# BOARD1A.net
KiCad netlist of a schematic drawn in EAGLE
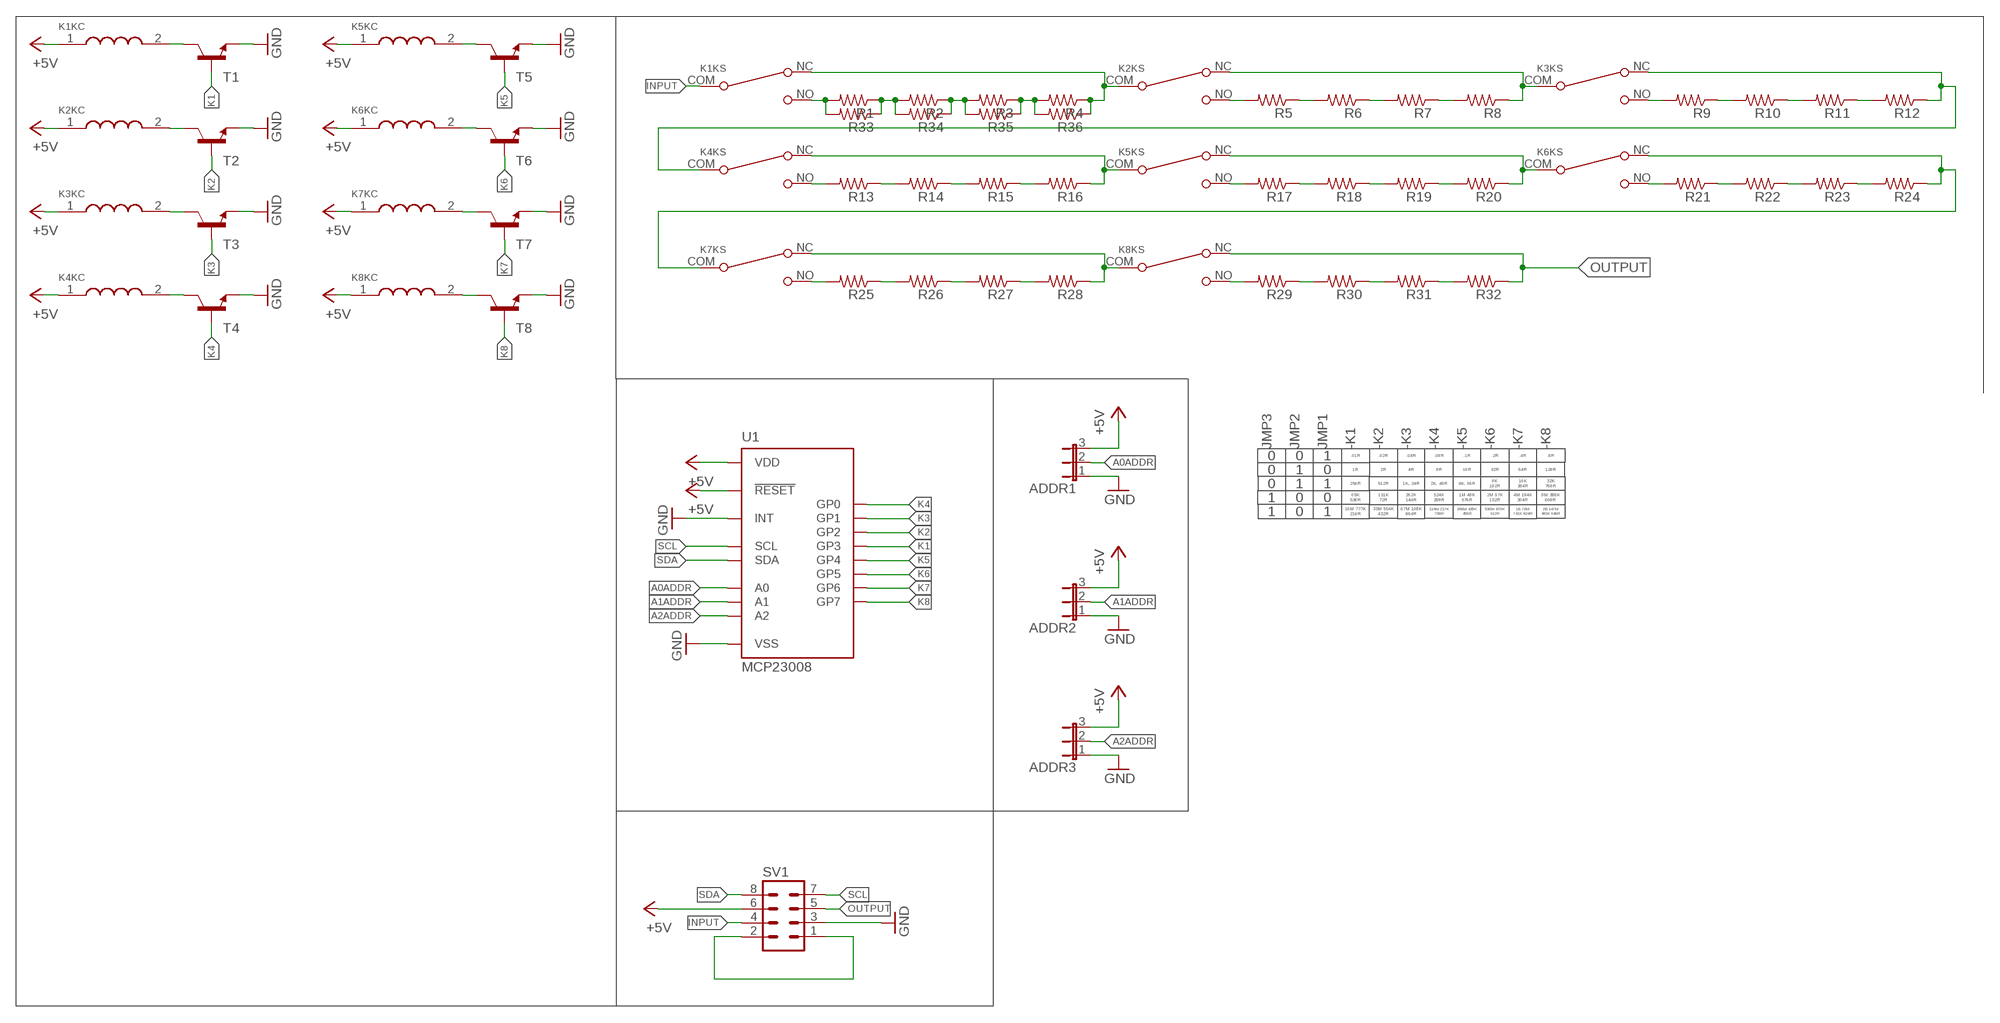
[diagram p0: schematic, sheet 1]

(export (version "E")
  (design (tool "Eeschema 10.0.6"))
  (components
    (comp (ref "ADDR1")
      (value "JP2E")
      (footprint "eagle-import:JP2")
      (libsource (lib "eagle-import") (part "JP2E"))
    )
    (comp (ref "ADDR2")
      (value "JP2E")
      (footprint "eagle-import:JP2")
      (libsource (lib "eagle-import") (part "JP2E"))
    )
    (comp (ref "ADDR3")
      (value "JP2E")
      (footprint "eagle-import:JP2")
      (libsource (lib "eagle-import") (part "JP2E"))
    )
    (comp (ref "K1")
      (value "G5LE-1-VD DC12")
      (footprint "eagle-import:G5LE")
      (libsource (lib "eagle-import") (part "G5LE"))
    )
    (comp (ref "K2")
      (value "G5LE")
      (footprint "eagle-import:G5LE")
      (libsource (lib "eagle-import") (part "G5LE"))
    )
    (comp (ref "K3")
      (value "G5LE")
      (footprint "eagle-import:G5LE")
      (libsource (lib "eagle-import") (part "G5LE"))
    )
    (comp (ref "K4")
      (value "G5LE")
      (footprint "eagle-import:G5LE")
      (libsource (lib "eagle-import") (part "G5LE"))
    )
    (comp (ref "K5")
      (value "G5LE")
      (footprint "eagle-import:G5LE")
      (libsource (lib "eagle-import") (part "G5LE"))
    )
    (comp (ref "K6")
      (value "G5LE")
      (footprint "eagle-import:G5LE")
      (libsource (lib "eagle-import") (part "G5LE"))
    )
    (comp (ref "K7")
      (value "G5LE")
      (footprint "eagle-import:G5LE")
      (libsource (lib "eagle-import") (part "G5LE"))
    )
    (comp (ref "K8")
      (value "G5LE")
      (footprint "eagle-import:G5LE")
      (libsource (lib "eagle-import") (part "G5LE"))
    )
    (comp (ref "R1")
      (value "R-US_0207/12")
      (footprint "eagle-import:0207_12")
      (libsource (lib "eagle-import") (part "R-US_0207/12"))
    )
    (comp (ref "R2")
      (value "R-US_0207/12")
      (footprint "eagle-import:0207_12")
      (libsource (lib "eagle-import") (part "R-US_0207/12"))
    )
    (comp (ref "R3")
      (value "R-US_0207/12")
      (footprint "eagle-import:0207_12")
      (libsource (lib "eagle-import") (part "R-US_0207/12"))
    )
    (comp (ref "R4")
      (value "R-US_0207/12")
      (footprint "eagle-import:0207_12")
      (libsource (lib "eagle-import") (part "R-US_0207/12"))
    )
    (comp (ref "R5")
      (value "R-US_0207/12")
      (footprint "eagle-import:0207_12")
      (libsource (lib "eagle-import") (part "R-US_0207/12"))
    )
    (comp (ref "R6")
      (value "R-US_0207/12")
      (footprint "eagle-import:0207_12")
      (libsource (lib "eagle-import") (part "R-US_0207/12"))
    )
    (comp (ref "R7")
      (value "R-US_0207/12")
      (footprint "eagle-import:0207_12")
      (libsource (lib "eagle-import") (part "R-US_0207/12"))
    )
    (comp (ref "R8")
      (value "R-US_0207/12")
      (footprint "eagle-import:0207_12")
      (libsource (lib "eagle-import") (part "R-US_0207/12"))
    )
    (comp (ref "R9")
      (value "R-US_0207/12")
      (footprint "eagle-import:0207_12")
      (libsource (lib "eagle-import") (part "R-US_0207/12"))
    )
    (comp (ref "R10")
      (value "R-US_0207/12")
      (footprint "eagle-import:0207_12")
      (libsource (lib "eagle-import") (part "R-US_0207/12"))
    )
    (comp (ref "R11")
      (value "R-US_0207/12")
      (footprint "eagle-import:0207_12")
      (libsource (lib "eagle-import") (part "R-US_0207/12"))
    )
    (comp (ref "R12")
      (value "R-US_0207/12")
      (footprint "eagle-import:0207_12")
      (libsource (lib "eagle-import") (part "R-US_0207/12"))
    )
    (comp (ref "R13")
      (value "R-US_0207/12")
      (footprint "eagle-import:0207_12")
      (libsource (lib "eagle-import") (part "R-US_0207/12"))
    )
    (comp (ref "R14")
      (value "R-US_0207/12")
      (footprint "eagle-import:0207_12")
      (libsource (lib "eagle-import") (part "R-US_0207/12"))
    )
    (comp (ref "R15")
      (value "R-US_0207/12")
      (footprint "eagle-import:0207_12")
      (libsource (lib "eagle-import") (part "R-US_0207/12"))
    )
    (comp (ref "R16")
      (value "R-US_0207/12")
      (footprint "eagle-import:0207_12")
      (libsource (lib "eagle-import") (part "R-US_0207/12"))
    )
    (comp (ref "R17")
      (value "R-US_0207/12")
      (footprint "eagle-import:0207_12")
      (libsource (lib "eagle-import") (part "R-US_0207/12"))
    )
    (comp (ref "R18")
      (value "R-US_0207/12")
      (footprint "eagle-import:0207_12")
      (libsource (lib "eagle-import") (part "R-US_0207/12"))
    )
    (comp (ref "R19")
      (value "R-US_0207/12")
      (footprint "eagle-import:0207_12")
      (libsource (lib "eagle-import") (part "R-US_0207/12"))
    )
    (comp (ref "R20")
      (value "R-US_0207/12")
      (footprint "eagle-import:0207_12")
      (libsource (lib "eagle-import") (part "R-US_0207/12"))
    )
    (comp (ref "R21")
      (value "R-US_0207/12")
      (footprint "eagle-import:0207_12")
      (libsource (lib "eagle-import") (part "R-US_0207/12"))
    )
    (comp (ref "R22")
      (value "R-US_0207/12")
      (footprint "eagle-import:0207_12")
      (libsource (lib "eagle-import") (part "R-US_0207/12"))
    )
    (comp (ref "R23")
      (value "R-US_0207/12")
      (footprint "eagle-import:0207_12")
      (libsource (lib "eagle-import") (part "R-US_0207/12"))
    )
    (comp (ref "R24")
      (value "R-US_0207/12")
      (footprint "eagle-import:0207_12")
      (libsource (lib "eagle-import") (part "R-US_0207/12"))
    )
    (comp (ref "R25")
      (value "R-US_0207/12")
      (footprint "eagle-import:0207_12")
      (libsource (lib "eagle-import") (part "R-US_0207/12"))
    )
    (comp (ref "R26")
      (value "R-US_0207/12")
      (footprint "eagle-import:0207_12")
      (libsource (lib "eagle-import") (part "R-US_0207/12"))
    )
    (comp (ref "R27")
      (value "R-US_0207/12")
      (footprint "eagle-import:0207_12")
      (libsource (lib "eagle-import") (part "R-US_0207/12"))
    )
    (comp (ref "R28")
      (value "R-US_0207/12")
      (footprint "eagle-import:0207_12")
      (libsource (lib "eagle-import") (part "R-US_0207/12"))
    )
    (comp (ref "R29")
      (value "R-US_0207/12")
      (footprint "eagle-import:0207_12")
      (libsource (lib "eagle-import") (part "R-US_0207/12"))
    )
    (comp (ref "R30")
      (value "R-US_0207/12")
      (footprint "eagle-import:0207_12")
      (libsource (lib "eagle-import") (part "R-US_0207/12"))
    )
    (comp (ref "R31")
      (value "R-US_0207/12")
      (footprint "eagle-import:0207_12")
      (libsource (lib "eagle-import") (part "R-US_0207/12"))
    )
    (comp (ref "R32")
      (value "R-US_0207/12")
      (footprint "eagle-import:0207_12")
      (libsource (lib "eagle-import") (part "R-US_0207/12"))
    )
    (comp (ref "R33")
      (value "RESISTOR1206")
      (footprint "eagle-import:1206")
      (libsource (lib "eagle-import") (part "RESISTOR1206"))
    )
    (comp (ref "R34")
      (value "RESISTOR1206")
      (footprint "eagle-import:1206")
      (libsource (lib "eagle-import") (part "RESISTOR1206"))
    )
    (comp (ref "R35")
      (value "RESISTOR1206")
      (footprint "eagle-import:1206")
      (libsource (lib "eagle-import") (part "RESISTOR1206"))
    )
    (comp (ref "R36")
      (value "RESISTOR1206")
      (footprint "eagle-import:1206")
      (libsource (lib "eagle-import") (part "RESISTOR1206"))
    )
    (comp (ref "SV1")
      (value "MA04-2")
      (footprint "eagle-import:MA04-2")
      (libsource (lib "eagle-import") (part "MA04-2"))
    )
    (comp (ref "T1")
      (value "MMUN2211LT1-NPN-SC59-BEC")
      (footprint "eagle-import:SC59-BEC")
      (libsource (lib "eagle-import") (part "-NPN-SC59-BECMMUN2211LT1"))
    )
    (comp (ref "T2")
      (value "MMUN2211LT1-NPN-SC59-BEC")
      (footprint "eagle-import:SC59-BEC")
      (libsource (lib "eagle-import") (part "-NPN-SC59-BECMMUN2211LT1"))
    )
    (comp (ref "T3")
      (value "MMUN2211LT1-NPN-SC59-BEC")
      (footprint "eagle-import:SC59-BEC")
      (libsource (lib "eagle-import") (part "-NPN-SC59-BECMMUN2211LT1"))
    )
    (comp (ref "T4")
      (value "MMUN2211LT1-NPN-SC59-BEC")
      (footprint "eagle-import:SC59-BEC")
      (libsource (lib "eagle-import") (part "-NPN-SC59-BECMMUN2211LT1"))
    )
    (comp (ref "T5")
      (value "MMUN2211LT1-NPN-SC59-BEC")
      (footprint "eagle-import:SC59-BEC")
      (libsource (lib "eagle-import") (part "-NPN-SC59-BECMMUN2211LT1"))
    )
    (comp (ref "T6")
      (value "MMUN2211LT1-NPN-SC59-BEC")
      (footprint "eagle-import:SC59-BEC")
      (libsource (lib "eagle-import") (part "-NPN-SC59-BECMMUN2211LT1"))
    )
    (comp (ref "T7")
      (value "MMUN2211LT1-NPN-SC59-BEC")
      (footprint "eagle-import:SC59-BEC")
      (libsource (lib "eagle-import") (part "-NPN-SC59-BECMMUN2211LT1"))
    )
    (comp (ref "T8")
      (value "MMUN2211LT1-NPN-SC59-BEC")
      (footprint "eagle-import:SC59-BEC")
      (libsource (lib "eagle-import") (part "-NPN-SC59-BECMMUN2211LT1"))
    )
    (comp (ref "U1")
      (value "MCP23008")
      (footprint "eagle-import:SOIC")
      (libsource (lib "eagle-import") (part "MCP23008"))
    )
  )
  (nets
    (net (code "1") (name "+5V") (class "Default")
      (node (ref "ADDR1") (pin "3") (pinfunction "3_3") (pintype "passive"))
      (node (ref "ADDR2") (pin "3") (pinfunction "3_3") (pintype "passive"))
      (node (ref "ADDR3") (pin "3") (pinfunction "3_3") (pintype "passive"))
      (node (ref "K1") (pin "1") (pinfunction "COILA_1") (pintype "bidirectional"))
      (node (ref "K2") (pin "1") (pinfunction "COILA_1") (pintype "bidirectional"))
      (node (ref "K3") (pin "1") (pinfunction "COILA_1") (pintype "bidirectional"))
      (node (ref "K4") (pin "1") (pinfunction "COILA_1") (pintype "bidirectional"))
      (node (ref "K5") (pin "1") (pinfunction "COILA_1") (pintype "bidirectional"))
      (node (ref "K6") (pin "1") (pinfunction "COILA_1") (pintype "bidirectional"))
      (node (ref "K7") (pin "1") (pinfunction "COILA_1") (pintype "bidirectional"))
      (node (ref "K8") (pin "1") (pinfunction "COILA_1") (pintype "bidirectional"))
      (node (ref "SV1") (pin "6") (pinfunction "6_6") (pintype "passive"))
      (node (ref "U1") (pin "P$18") (pinfunction "VDD_P$18") (pintype "power_in"))
      (node (ref "U1") (pin "P$6") (pinfunction "~{RESET}_P$6") (pintype "input"))
    )
    (net (code "2") (name "A0ADDR") (class "Default")
      (node (ref "ADDR1") (pin "2") (pinfunction "2_2") (pintype "passive"))
      (node (ref "U1") (pin "P$5") (pinfunction "A0_P$5") (pintype "input"))
    )
    (net (code "3") (name "A1ADDR") (class "Default")
      (node (ref "ADDR2") (pin "2") (pinfunction "2_2") (pintype "passive"))
      (node (ref "U1") (pin "P$4") (pinfunction "A1_P$4") (pintype "input"))
    )
    (net (code "4") (name "A2ADDR") (class "Default")
      (node (ref "ADDR3") (pin "2") (pinfunction "2_2") (pintype "passive"))
      (node (ref "U1") (pin "P$3") (pinfunction "A2_P$3") (pintype "input"))
    )
    (net (code "5") (name "GND") (class "Default")
      (node (ref "ADDR1") (pin "1") (pinfunction "1_1") (pintype "passive"))
      (node (ref "ADDR2") (pin "1") (pinfunction "1_1") (pintype "passive"))
      (node (ref "ADDR3") (pin "1") (pinfunction "1_1") (pintype "passive"))
      (node (ref "SV1") (pin "3") (pinfunction "3_3") (pintype "passive"))
      (node (ref "T1") (pin "E") (pinfunction "E_E") (pintype "passive"))
      (node (ref "T2") (pin "E") (pinfunction "E_E") (pintype "passive"))
      (node (ref "T3") (pin "E") (pinfunction "E_E") (pintype "passive"))
      (node (ref "T4") (pin "E") (pinfunction "E_E") (pintype "passive"))
      (node (ref "T5") (pin "E") (pinfunction "E_E") (pintype "passive"))
      (node (ref "T6") (pin "E") (pinfunction "E_E") (pintype "passive"))
      (node (ref "T7") (pin "E") (pinfunction "E_E") (pintype "passive"))
      (node (ref "T8") (pin "E") (pinfunction "E_E") (pintype "passive"))
      (node (ref "U1") (pin "P$8") (pinfunction "INT_P$8") (pintype "output"))
      (node (ref "U1") (pin "P$9") (pinfunction "VSS_P$9") (pintype "power_in"))
    )
    (net (code "6") (name "INPUT") (class "Default")
      (node (ref "K1") (pin "COM") (pinfunction "P$COM_COM") (pintype "bidirectional"))
      (node (ref "SV1") (pin "4") (pinfunction "4_4") (pintype "passive"))
    )
    (net (code "7") (name "K1") (class "Default")
      (node (ref "T1") (pin "B") (pinfunction "B_B") (pintype "passive"))
      (node (ref "U1") (pin "P$13") (pinfunction "GP3_P$13") (pintype "bidirectional"))
    )
    (net (code "8") (name "K2") (class "Default")
      (node (ref "T2") (pin "B") (pinfunction "B_B") (pintype "passive"))
      (node (ref "U1") (pin "P$12") (pinfunction "GP2_P$12") (pintype "bidirectional"))
    )
    (net (code "9") (name "K3") (class "Default")
      (node (ref "T3") (pin "B") (pinfunction "B_B") (pintype "passive"))
      (node (ref "U1") (pin "P$11") (pinfunction "GP1_P$11") (pintype "bidirectional"))
    )
    (net (code "10") (name "K4") (class "Default")
      (node (ref "T4") (pin "B") (pinfunction "B_B") (pintype "passive"))
      (node (ref "U1") (pin "P$10") (pinfunction "GP0_P$10") (pintype "bidirectional"))
    )
    (net (code "11") (name "K5") (class "Default")
      (node (ref "T5") (pin "B") (pinfunction "B_B") (pintype "passive"))
      (node (ref "U1") (pin "P$14") (pinfunction "GP4_P$14") (pintype "bidirectional"))
    )
    (net (code "12") (name "K6") (class "Default")
      (node (ref "T6") (pin "B") (pinfunction "B_B") (pintype "passive"))
      (node (ref "U1") (pin "P$15") (pinfunction "GP5_P$15") (pintype "bidirectional"))
    )
    (net (code "13") (name "K7") (class "Default")
      (node (ref "T7") (pin "B") (pinfunction "B_B") (pintype "passive"))
      (node (ref "U1") (pin "P$16") (pinfunction "GP6_P$16") (pintype "bidirectional"))
    )
    (net (code "14") (name "K8") (class "Default")
      (node (ref "T8") (pin "B") (pinfunction "B_B") (pintype "passive"))
      (node (ref "U1") (pin "P$17") (pinfunction "GP7_P$17") (pintype "bidirectional"))
    )
    (net (code "15") (name "Net-(K1A-COILB)") (class "Default")
      (node (ref "K1") (pin "2") (pinfunction "COILB_2") (pintype "bidirectional"))
      (node (ref "T1") (pin "C") (pinfunction "C_C") (pintype "passive"))
    )
    (net (code "16") (name "Net-(K1B-P$NC)") (class "Default")
      (node (ref "K1") (pin "NC") (pinfunction "P$NC_NC") (pintype "bidirectional"))
      (node (ref "K2") (pin "COM") (pinfunction "P$COM_COM") (pintype "bidirectional"))
      (node (ref "R36") (pin "1") (pinfunction "1_1") (pintype "passive"))
      (node (ref "R4") (pin "1") (pinfunction "1_1") (pintype "passive"))
    )
    (net (code "17") (name "Net-(K1B-P$NO)") (class "Default")
      (node (ref "K1") (pin "NO") (pinfunction "P$NO_NO") (pintype "bidirectional"))
      (node (ref "R1") (pin "2") (pinfunction "2_2") (pintype "passive"))
      (node (ref "R33") (pin "2") (pinfunction "2_2") (pintype "passive"))
    )
    (net (code "18") (name "Net-(K2A-COILB)") (class "Default")
      (node (ref "K2") (pin "2") (pinfunction "COILB_2") (pintype "bidirectional"))
      (node (ref "T2") (pin "C") (pinfunction "C_C") (pintype "passive"))
    )
    (net (code "19") (name "Net-(K2B-P$NC)") (class "Default")
      (node (ref "K2") (pin "NC") (pinfunction "P$NC_NC") (pintype "bidirectional"))
      (node (ref "K3") (pin "COM") (pinfunction "P$COM_COM") (pintype "bidirectional"))
      (node (ref "R8") (pin "1") (pinfunction "1_1") (pintype "passive"))
    )
    (net (code "20") (name "Net-(K2B-P$NO)") (class "Default")
      (node (ref "K2") (pin "NO") (pinfunction "P$NO_NO") (pintype "bidirectional"))
      (node (ref "R5") (pin "2") (pinfunction "2_2") (pintype "passive"))
    )
    (net (code "21") (name "Net-(K3A-COILB)") (class "Default")
      (node (ref "K3") (pin "2") (pinfunction "COILB_2") (pintype "bidirectional"))
      (node (ref "T3") (pin "C") (pinfunction "C_C") (pintype "passive"))
    )
    (net (code "22") (name "Net-(K3B-P$NC)") (class "Default")
      (node (ref "K3") (pin "NC") (pinfunction "P$NC_NC") (pintype "bidirectional"))
      (node (ref "K4") (pin "COM") (pinfunction "P$COM_COM") (pintype "bidirectional"))
      (node (ref "R12") (pin "1") (pinfunction "1_1") (pintype "passive"))
    )
    (net (code "23") (name "Net-(K3B-P$NO)") (class "Default")
      (node (ref "K3") (pin "NO") (pinfunction "P$NO_NO") (pintype "bidirectional"))
      (node (ref "R9") (pin "2") (pinfunction "2_2") (pintype "passive"))
    )
    (net (code "24") (name "Net-(K4A-COILB)") (class "Default")
      (node (ref "K4") (pin "2") (pinfunction "COILB_2") (pintype "bidirectional"))
      (node (ref "T4") (pin "C") (pinfunction "C_C") (pintype "passive"))
    )
    (net (code "25") (name "Net-(K4B-P$NC)") (class "Default")
      (node (ref "K4") (pin "NC") (pinfunction "P$NC_NC") (pintype "bidirectional"))
      (node (ref "K5") (pin "COM") (pinfunction "P$COM_COM") (pintype "bidirectional"))
      (node (ref "R16") (pin "1") (pinfunction "1_1") (pintype "passive"))
    )
    (net (code "26") (name "Net-(K4B-P$NO)") (class "Default")
      (node (ref "K4") (pin "NO") (pinfunction "P$NO_NO") (pintype "bidirectional"))
      (node (ref "R13") (pin "2") (pinfunction "2_2") (pintype "passive"))
    )
    (net (code "27") (name "Net-(K5A-COILB)") (class "Default")
      (node (ref "K5") (pin "2") (pinfunction "COILB_2") (pintype "bidirectional"))
      (node (ref "T5") (pin "C") (pinfunction "C_C") (pintype "passive"))
    )
    (net (code "28") (name "Net-(K5B-P$NC)") (class "Default")
      (node (ref "K5") (pin "NC") (pinfunction "P$NC_NC") (pintype "bidirectional"))
      (node (ref "K6") (pin "COM") (pinfunction "P$COM_COM") (pintype "bidirectional"))
      (node (ref "R20") (pin "1") (pinfunction "1_1") (pintype "passive"))
    )
    (net (code "29") (name "Net-(K5B-P$NO)") (class "Default")
      (node (ref "K5") (pin "NO") (pinfunction "P$NO_NO") (pintype "bidirectional"))
      (node (ref "R17") (pin "2") (pinfunction "2_2") (pintype "passive"))
    )
    (net (code "30") (name "Net-(K6A-COILB)") (class "Default")
      (node (ref "K6") (pin "2") (pinfunction "COILB_2") (pintype "bidirectional"))
      (node (ref "T6") (pin "C") (pinfunction "C_C") (pintype "passive"))
    )
    (net (code "31") (name "Net-(K6B-P$NC)") (class "Default")
      (node (ref "K6") (pin "NC") (pinfunction "P$NC_NC") (pintype "bidirectional"))
      (node (ref "K7") (pin "COM") (pinfunction "P$COM_COM") (pintype "bidirectional"))
      (node (ref "R24") (pin "1") (pinfunction "1_1") (pintype "passive"))
    )
    (net (code "32") (name "Net-(K6B-P$NO)") (class "Default")
      (node (ref "K6") (pin "NO") (pinfunction "P$NO_NO") (pintype "bidirectional"))
      (node (ref "R21") (pin "2") (pinfunction "2_2") (pintype "passive"))
    )
    (net (code "33") (name "Net-(K7A-COILB)") (class "Default")
      (node (ref "K7") (pin "2") (pinfunction "COILB_2") (pintype "bidirectional"))
      (node (ref "T7") (pin "C") (pinfunction "C_C") (pintype "passive"))
    )
    (net (code "34") (name "Net-(K7B-P$NC)") (class "Default")
      (node (ref "K7") (pin "NC") (pinfunction "P$NC_NC") (pintype "bidirectional"))
      (node (ref "K8") (pin "COM") (pinfunction "P$COM_COM") (pintype "bidirectional"))
      (node (ref "R28") (pin "1") (pinfunction "1_1") (pintype "passive"))
    )
    (net (code "35") (name "Net-(K7B-P$NO)") (class "Default")
      (node (ref "K7") (pin "NO") (pinfunction "P$NO_NO") (pintype "bidirectional"))
      (node (ref "R25") (pin "2") (pinfunction "2_2") (pintype "passive"))
    )
    (net (code "36") (name "Net-(K8A-COILB)") (class "Default")
      (node (ref "K8") (pin "2") (pinfunction "COILB_2") (pintype "bidirectional"))
      (node (ref "T8") (pin "C") (pinfunction "C_C") (pintype "passive"))
    )
    (net (code "37") (name "Net-(K8B-P$NO)") (class "Default")
      (node (ref "K8") (pin "NO") (pinfunction "P$NO_NO") (pintype "bidirectional"))
      (node (ref "R29") (pin "2") (pinfunction "2_2") (pintype "passive"))
    )
    (net (code "38") (name "Net-(R1-Pad1)") (class "Default")
      (node (ref "R1") (pin "1") (pinfunction "1_1") (pintype "passive"))
      (node (ref "R2") (pin "2") (pinfunction "2_2") (pintype "passive"))
      (node (ref "R33") (pin "1") (pinfunction "1_1") (pintype "passive"))
      (node (ref "R34") (pin "2") (pinfunction "2_2") (pintype "passive"))
    )
    (net (code "39") (name "Net-(R2-Pad1)") (class "Default")
      (node (ref "R2") (pin "1") (pinfunction "1_1") (pintype "passive"))
      (node (ref "R3") (pin "2") (pinfunction "2_2") (pintype "passive"))
      (node (ref "R34") (pin "1") (pinfunction "1_1") (pintype "passive"))
      (node (ref "R35") (pin "2") (pinfunction "2_2") (pintype "passive"))
    )
    (net (code "40") (name "Net-(R3-Pad1)") (class "Default")
      (node (ref "R3") (pin "1") (pinfunction "1_1") (pintype "passive"))
      (node (ref "R35") (pin "1") (pinfunction "1_1") (pintype "passive"))
      (node (ref "R36") (pin "2") (pinfunction "2_2") (pintype "passive"))
      (node (ref "R4") (pin "2") (pinfunction "2_2") (pintype "passive"))
    )
    (net (code "41") (name "Net-(R5-Pad1)") (class "Default")
      (node (ref "R5") (pin "1") (pinfunction "1_1") (pintype "passive"))
      (node (ref "R6") (pin "2") (pinfunction "2_2") (pintype "passive"))
    )
    (net (code "42") (name "Net-(R6-Pad1)") (class "Default")
      (node (ref "R6") (pin "1") (pinfunction "1_1") (pintype "passive"))
      (node (ref "R7") (pin "2") (pinfunction "2_2") (pintype "passive"))
    )
    (net (code "43") (name "Net-(R7-Pad1)") (class "Default")
      (node (ref "R7") (pin "1") (pinfunction "1_1") (pintype "passive"))
      (node (ref "R8") (pin "2") (pinfunction "2_2") (pintype "passive"))
    )
    (net (code "44") (name "Net-(R10-Pad1)") (class "Default")
      (node (ref "R10") (pin "1") (pinfunction "1_1") (pintype "passive"))
      (node (ref "R11") (pin "2") (pinfunction "2_2") (pintype "passive"))
    )
    (net (code "45") (name "Net-(R10-Pad2)") (class "Default")
      (node (ref "R10") (pin "2") (pinfunction "2_2") (pintype "passive"))
      (node (ref "R9") (pin "1") (pinfunction "1_1") (pintype "passive"))
    )
    (net (code "46") (name "Net-(R11-Pad1)") (class "Default")
      (node (ref "R11") (pin "1") (pinfunction "1_1") (pintype "passive"))
      (node (ref "R12") (pin "2") (pinfunction "2_2") (pintype "passive"))
    )
    (net (code "47") (name "Net-(R13-Pad1)") (class "Default")
      (node (ref "R13") (pin "1") (pinfunction "1_1") (pintype "passive"))
      (node (ref "R14") (pin "2") (pinfunction "2_2") (pintype "passive"))
    )
    (net (code "48") (name "Net-(R14-Pad1)") (class "Default")
      (node (ref "R14") (pin "1") (pinfunction "1_1") (pintype "passive"))
      (node (ref "R15") (pin "2") (pinfunction "2_2") (pintype "passive"))
    )
    (net (code "49") (name "Net-(R15-Pad1)") (class "Default")
      (node (ref "R15") (pin "1") (pinfunction "1_1") (pintype "passive"))
      (node (ref "R16") (pin "2") (pinfunction "2_2") (pintype "passive"))
    )
    (net (code "50") (name "Net-(R17-Pad1)") (class "Default")
      (node (ref "R17") (pin "1") (pinfunction "1_1") (pintype "passive"))
      (node (ref "R18") (pin "2") (pinfunction "2_2") (pintype "passive"))
    )
    (net (code "51") (name "Net-(R18-Pad1)") (class "Default")
      (node (ref "R18") (pin "1") (pinfunction "1_1") (pintype "passive"))
      (node (ref "R19") (pin "2") (pinfunction "2_2") (pintype "passive"))
    )
    (net (code "52") (name "Net-(R19-Pad1)") (class "Default")
      (node (ref "R19") (pin "1") (pinfunction "1_1") (pintype "passive"))
      (node (ref "R20") (pin "2") (pinfunction "2_2") (pintype "passive"))
    )
    (net (code "53") (name "Net-(R21-Pad1)") (class "Default")
      (node (ref "R21") (pin "1") (pinfunction "1_1") (pintype "passive"))
      (node (ref "R22") (pin "2") (pinfunction "2_2") (pintype "passive"))
    )
    (net (code "54") (name "Net-(R22-Pad1)") (class "Default")
      (node (ref "R22") (pin "1") (pinfunction "1_1") (pintype "passive"))
      (node (ref "R23") (pin "2") (pinfunction "2_2") (pintype "passive"))
    )
    (net (code "55") (name "Net-(R23-Pad1)") (class "Default")
      (node (ref "R23") (pin "1") (pinfunction "1_1") (pintype "passive"))
      (node (ref "R24") (pin "2") (pinfunction "2_2") (pintype "passive"))
    )
    (net (code "56") (name "Net-(R25-Pad1)") (class "Default")
      (node (ref "R25") (pin "1") (pinfunction "1_1") (pintype "passive"))
      (node (ref "R26") (pin "2") (pinfunction "2_2") (pintype "passive"))
    )
    (net (code "57") (name "Net-(R26-Pad1)") (class "Default")
      (node (ref "R26") (pin "1") (pinfunction "1_1") (pintype "passive"))
      (node (ref "R27") (pin "2") (pinfunction "2_2") (pintype "passive"))
    )
    (net (code "58") (name "Net-(R27-Pad1)") (class "Default")
      (node (ref "R27") (pin "1") (pinfunction "1_1") (pintype "passive"))
      (node (ref "R28") (pin "2") (pinfunction "2_2") (pintype "passive"))
    )
    (net (code "59") (name "Net-(R29-Pad1)") (class "Default")
      (node (ref "R29") (pin "1") (pinfunction "1_1") (pintype "passive"))
      (node (ref "R30") (pin "2") (pinfunction "2_2") (pintype "passive"))
    )
    (net (code "60") (name "Net-(R30-Pad1)") (class "Default")
      (node (ref "R30") (pin "1") (pinfunction "1_1") (pintype "passive"))
      (node (ref "R31") (pin "2") (pinfunction "2_2") (pintype "passive"))
    )
    (net (code "61") (name "Net-(R31-Pad1)") (class "Default")
      (node (ref "R31") (pin "1") (pinfunction "1_1") (pintype "passive"))
      (node (ref "R32") (pin "2") (pinfunction "2_2") (pintype "passive"))
    )
    (net (code "62") (name "Net-(SV1-Pad1)") (class "Default")
      (node (ref "SV1") (pin "1") (pinfunction "1_1") (pintype "passive"))
      (node (ref "SV1") (pin "2") (pinfunction "2_2") (pintype "passive"))
    )
    (net (code "63") (name "OUTPUT") (class "Default")
      (node (ref "K8") (pin "NC") (pinfunction "P$NC_NC") (pintype "bidirectional"))
      (node (ref "R32") (pin "1") (pinfunction "1_1") (pintype "passive"))
      (node (ref "SV1") (pin "5") (pinfunction "5_5") (pintype "passive"))
    )
    (net (code "64") (name "SCL") (class "Default")
      (node (ref "SV1") (pin "7") (pinfunction "7_7") (pintype "passive"))
      (node (ref "U1") (pin "P$1") (pinfunction "SCL_P$1") (pintype "input"))
    )
    (net (code "65") (name "SDA") (class "Default")
      (node (ref "SV1") (pin "8") (pinfunction "8_8") (pintype "passive"))
      (node (ref "U1") (pin "P$2") (pinfunction "SDA_P$2") (pintype "bidirectional"))
    )
  )
)
